# STM32F407.net
KiCad netlist of a schematic drawn in Altium Designer
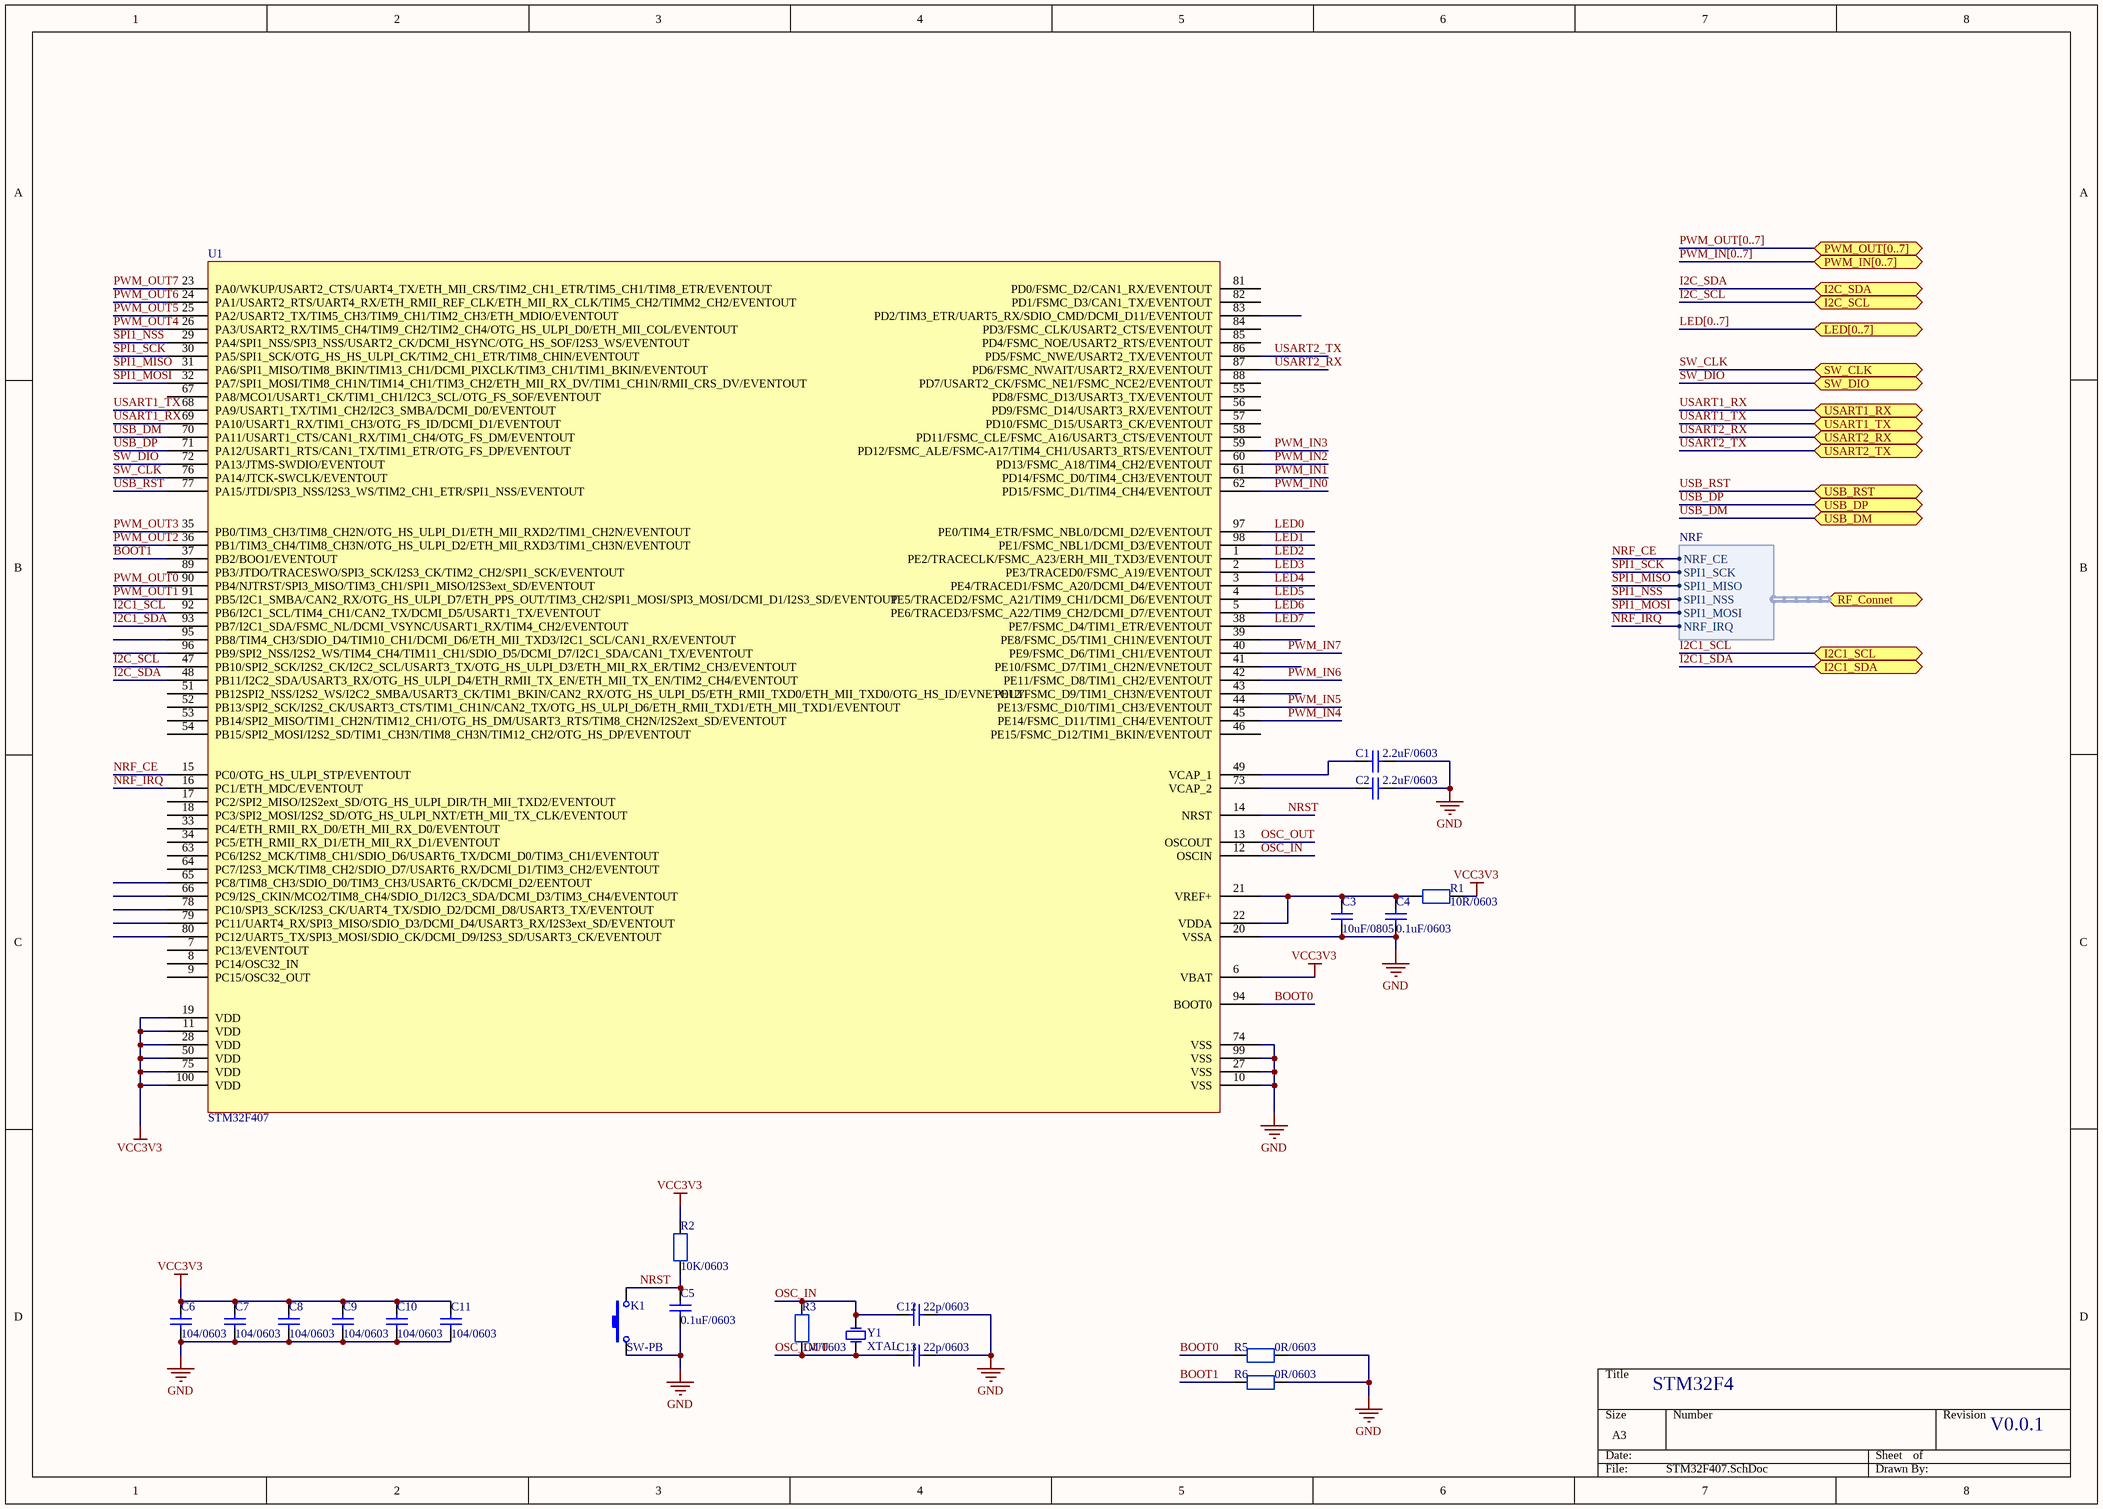
[diagram p0: STM32F407.SchDoc]

(export (version "E")
  (design (tool "Eeschema 10.0.6"))
  (components
    (comp (ref "C1")
      (value "2.2uF/0603")
      (footprint "C0603")
      (description "无极性贴片电容")
      (libsource (lib "常用原件") (part "CAP"))
    )
    (comp (ref "C2")
      (value "2.2uF/0603")
      (footprint "C0603")
      (description "无极性贴片电容")
      (libsource (lib "常用原件") (part "CAP"))
    )
    (comp (ref "C3")
      (value "10uF/0805")
      (footprint "C0805")
      (description "无极性贴片电容")
      (libsource (lib "常用原件") (part "CAP"))
    )
    (comp (ref "C4")
      (value "0.1uF/0603")
      (footprint "C0603")
      (description "无极性贴片电容")
      (libsource (lib "常用原件") (part "CAP"))
    )
    (comp (ref "C5")
      (value "0.1uF/0603")
      (footprint "C0603")
      (description "无极性贴片电容")
      (libsource (lib "常用原件") (part "CAP"))
    )
    (comp (ref "C6")
      (value "104/0603")
      (footprint "C0603")
      (description "无极性贴片电容")
      (libsource (lib "常用原件") (part "CAP"))
    )
    (comp (ref "C7")
      (value "104/0603")
      (footprint "C0603")
      (description "无极性贴片电容")
      (libsource (lib "常用原件") (part "CAP"))
    )
    (comp (ref "C8")
      (value "104/0603")
      (footprint "C0603")
      (description "无极性贴片电容")
      (libsource (lib "常用原件") (part "CAP"))
    )
    (comp (ref "C9")
      (value "104/0603")
      (footprint "C0603")
      (description "无极性贴片电容")
      (libsource (lib "常用原件") (part "CAP"))
    )
    (comp (ref "C10")
      (value "104/0603")
      (footprint "C0603")
      (description "无极性贴片电容")
      (libsource (lib "常用原件") (part "CAP"))
    )
    (comp (ref "C11")
      (value "104/0603")
      (footprint "C0603")
      (description "无极性贴片电容")
      (libsource (lib "常用原件") (part "CAP"))
    )
    (comp (ref "C12")
      (value "22p/0603")
      (footprint "C0603")
      (description "无极性贴片电容")
      (libsource (lib "常用原件") (part "CAP"))
    )
    (comp (ref "C13")
      (value "22p/0603")
      (footprint "C0603")
      (description "无极性贴片电容")
      (libsource (lib "常用原件") (part "CAP"))
    )
    (comp (ref "K1") (value "SW-PB") (footprint "SW-PB-A1") (libsource (lib "常用原件") (part "SW-PB")))
    (comp (ref "R1") (value "10R/0603") (footprint "R0603") (libsource (lib "常用原件") (part "RES")))
    (comp (ref "R2") (value "10K/0603") (footprint "R0603") (libsource (lib "常用原件") (part "RES")))
    (comp (ref "R3") (value "1M/0603") (footprint "R0603") (libsource (lib "常用原件") (part "RES")))
    (comp (ref "R5") (value "0R/0603") (footprint "R0603") (libsource (lib "常用原件") (part "RES")))
    (comp (ref "R6") (value "0R/0603") (footprint "R0402") (libsource (lib "常用原件") (part "RES")))
    (comp (ref "U1")
      (value "STM32F407")
      (footprint "LQFP100-N")
      (description "STM32F407VGT6")
      (libsource (lib "Schlib1") (part "STM32F4"))
    )
    (comp (ref "Y1") (value "XTAL") (footprint "XTAL-3225") (libsource (lib "库原理") (part "XTAL")))
  )
  (nets
    (net (code "2") (name "/BOOT0") (class "Default")
      (node (ref "R5") (pin "1") (pinfunction "1_1") (pintype "passive"))
      (node (ref "U1") (pin "94") (pinfunction "BOOT0_94") (pintype "passive"))
    )
    (net (code "3") (name "/BOOT1") (class "Default")
      (node (ref "R6") (pin "1") (pinfunction "1_1") (pintype "passive"))
      (node (ref "U1") (pin "37") (pinfunction "PB2/BOO1/EVENTOUT_37") (pintype "passive"))
    )
    (net (code "4") (name "/I2C1_SCL") (class "Default")
      (node (ref "U1") (pin "92") (pinfunction "PB6/I2C1_SCL/TIM4_CH1/CAN2_TX/DCMI_D5/USART1_TX/EVENTOUT_92") (pintype "passive"))
    )
    (net (code "5") (name "/I2C1_SDA") (class "Default")
      (node (ref "U1") (pin "93") (pinfunction "PB7/I2C1_SDA/FSMC_NL/DCMI_VSYNC/USART1_RX/TIM4_CH2/EVENTOUT_93") (pintype "passive"))
    )
    (net (code "6") (name "/I2C_SCL") (class "Default")
      (node (ref "U1") (pin "47") (pinfunction "PB10/SPI2_SCK/I2S2_CK/I2C2_SCL/USART3_TX/OTG_HS_ULPI_D3/ETH_MII_RX_ER/TIM2_CH3/EVENTOUT_47") (pintype "passive"))
    )
    (net (code "7") (name "/I2C_SDA") (class "Default")
      (node (ref "U1") (pin "48") (pinfunction "PB11/I2C2_SDA/USART3_RX/OTG_HS_ULPI_D4/ETH_RMII_TX_EN/ETH_MII_TX_EN/TIM2_CH4/EVENTOUT_48") (pintype "passive"))
    )
    (net (code "8") (name "/LED0") (class "Default")
      (node (ref "U1") (pin "97") (pinfunction "PE0/TIM4_ETR/FSMC_NBL0/DCMI_D2/EVENTOUT_97") (pintype "passive"))
    )
    (net (code "9") (name "/LED1") (class "Default")
      (node (ref "U1") (pin "98") (pinfunction "PE1/FSMC_NBL1/DCMI_D3/EVENTOUT_98") (pintype "passive"))
    )
    (net (code "10") (name "/LED2") (class "Default")
      (node (ref "U1") (pin "1") (pinfunction "PE2/TRACECLK/FSMC_A23/ERH_MII_TXD3/EVENTOUT_1") (pintype "passive"))
    )
    (net (code "11") (name "/LED3") (class "Default")
      (node (ref "U1") (pin "2") (pinfunction "PE3/TRACED0/FSMC_A19/EVENTOUT_2") (pintype "passive"))
    )
    (net (code "12") (name "/LED4") (class "Default")
      (node (ref "U1") (pin "3") (pinfunction "PE4/TRACED1/FSMC_A20/DCMI_D4/EVENTOUT_3") (pintype "passive"))
    )
    (net (code "13") (name "/LED5") (class "Default")
      (node (ref "U1") (pin "4") (pinfunction "PE5/TRACED2/FSMC_A21/TIM9_CH1/DCMI_D6/EVENTOUT_4") (pintype "passive"))
    )
    (net (code "14") (name "/LED6") (class "Default")
      (node (ref "U1") (pin "5") (pinfunction "PE6/TRACED3/FSMC_A22/TIM9_CH2/DCMI_D7/EVENTOUT_5") (pintype "passive"))
    )
    (net (code "15") (name "/LED7") (class "Default")
      (node (ref "U1") (pin "38") (pinfunction "PE7/FSMC_D4/TIM1_ETR/EVENTOUT_38") (pintype "passive"))
    )
    (net (code "17") (name "/NRF_CE") (class "Default")
      (node (ref "U1") (pin "15") (pinfunction "PC0/OTG_HS_ULPI_STP/EVENTOUT_15") (pintype "passive"))
    )
    (net (code "18") (name "/NRF_IRQ") (class "Default")
      (node (ref "U1") (pin "16") (pinfunction "PC1/ETH_MDC/EVENTOUT_16") (pintype "passive"))
    )
    (net (code "19") (name "/NRST") (class "Default")
      (node (ref "C5") (pin "2") (pinfunction "2_2") (pintype "passive"))
      (node (ref "K1") (pin "2") (pinfunction "2_2") (pintype "passive"))
      (node (ref "R2") (pin "1") (pinfunction "1_1") (pintype "passive"))
      (node (ref "U1") (pin "14") (pinfunction "NRST_14") (pintype "passive"))
    )
    (net (code "20") (name "/OSC_IN") (class "Default")
      (node (ref "C12") (pin "2") (pinfunction "2_2") (pintype "passive"))
      (node (ref "R3") (pin "2") (pinfunction "2_2") (pintype "passive"))
      (node (ref "U1") (pin "12") (pinfunction "OSCIN_12") (pintype "passive"))
      (node (ref "Y1") (pin "2") (pinfunction "OSC2_2") (pintype "passive"))
    )
    (net (code "21") (name "/OSC_OUT") (class "Default")
      (node (ref "C13") (pin "2") (pinfunction "2_2") (pintype "passive"))
      (node (ref "R3") (pin "1") (pinfunction "1_1") (pintype "passive"))
      (node (ref "U1") (pin "13") (pinfunction "OSCOUT_13") (pintype "passive"))
      (node (ref "Y1") (pin "1") (pinfunction "OSC1_1") (pintype "passive"))
    )
    (net (code "22") (name "/PWM_IN0") (class "Default")
      (node (ref "U1") (pin "62") (pinfunction "PD15/FSMC_D1/TIM4_CH4/EVENTOUT_62") (pintype "passive"))
    )
    (net (code "23") (name "/PWM_IN1") (class "Default")
      (node (ref "U1") (pin "61") (pinfunction "PD14/FSMC_D0/TIM4_CH3/EVENTOUT_61") (pintype "passive"))
    )
    (net (code "24") (name "/PWM_IN2") (class "Default")
      (node (ref "U1") (pin "60") (pinfunction "PD13/FSMC_A18/TIM4_CH2/EVENTOUT_60") (pintype "passive"))
    )
    (net (code "25") (name "/PWM_IN3") (class "Default")
      (node (ref "U1") (pin "59") (pinfunction "PD12/FSMC_ALE/FSMC-A17/TIM4_CH1/USART3_RTS/EVENTOUT_59") (pintype "passive"))
    )
    (net (code "26") (name "/PWM_IN4") (class "Default")
      (node (ref "U1") (pin "45") (pinfunction "PE14/FSMC_D11/TIM1_CH4/EVENTOUT_45") (pintype "passive"))
    )
    (net (code "27") (name "/PWM_IN5") (class "Default")
      (node (ref "U1") (pin "44") (pinfunction "PE13/FSMC_D10/TIM1_CH3/EVENTOUT_44") (pintype "passive"))
    )
    (net (code "28") (name "/PWM_IN6") (class "Default")
      (node (ref "U1") (pin "42") (pinfunction "PE11/FSMC_D8/TIM1_CH2/EVENTOUT_42") (pintype "passive"))
    )
    (net (code "29") (name "/PWM_IN7") (class "Default")
      (node (ref "U1") (pin "40") (pinfunction "PE9/FSMC_D6/TIM1_CH1/EVENTOUT_40") (pintype "passive"))
    )
    (net (code "31") (name "/PWM_OUT0") (class "Default")
      (node (ref "U1") (pin "90") (pinfunction "PB4/NJTRST/SPI3_MISO/TIM3_CH1/SPI1_MISO/I2S3ext_SD/EVENTOUT_90") (pintype "passive"))
    )
    (net (code "32") (name "/PWM_OUT1") (class "Default")
      (node (ref "U1") (pin "91") (pinfunction "PB5/I2C1_SMBA/CAN2_RX/OTG_HS_ULPI_D7/ETH_PPS_OUT/TIM3_CH2/SPI1_MOSI/SPI3_MOSI/DCMI_D1/I2S3_SD/EVENTOUT_91") (pintype "passive"))
    )
    (net (code "33") (name "/PWM_OUT2") (class "Default")
      (node (ref "U1") (pin "36") (pinfunction "PB1/TIM3_CH4/TIM8_CH3N/OTG_HS_ULPI_D2/ETH_MII_RXD3/TIM1_CH3N/EVENTOUT_36") (pintype "passive"))
    )
    (net (code "34") (name "/PWM_OUT3") (class "Default")
      (node (ref "U1") (pin "35") (pinfunction "PB0/TIM3_CH3/TIM8_CH2N/OTG_HS_ULPI_D1/ETH_MII_RXD2/TIM1_CH2N/EVENTOUT_35") (pintype "passive"))
    )
    (net (code "35") (name "/PWM_OUT4") (class "Default")
      (node (ref "U1") (pin "26") (pinfunction "PA3/USART2_RX/TIM5_CH4/TIM9_CH2/TIM2_CH4/OTG_HS_ULPI_D0/ETH_MII_COL/EVENTOUT_26") (pintype "passive"))
    )
    (net (code "36") (name "/PWM_OUT5") (class "Default")
      (node (ref "U1") (pin "25") (pinfunction "PA2/USART2_TX/TIM5_CH3/TIM9_CH1/TIM2_CH3/ETH_MDIO/EVENTOUT_25") (pintype "passive"))
    )
    (net (code "37") (name "/PWM_OUT6") (class "Default")
      (node (ref "U1") (pin "24") (pinfunction "PA1/USART2_RTS/UART4_RX/ETH_RMII_REF_CLK/ETH_MII_RX_CLK/TIM5_CH2/TIMM2_CH2/EVENTOUT_24") (pintype "passive"))
    )
    (net (code "38") (name "/PWM_OUT7") (class "Default")
      (node (ref "U1") (pin "23") (pinfunction "PA0/WKUP/USART2_CTS/UART4_TX/ETH_MII_CRS/TIM2_CH1_ETR/TIM5_CH1/TIM8_ETR/EVENTOUT_23") (pintype "passive"))
    )
    (net (code "40") (name "/SPI1_MISO") (class "Default")
      (node (ref "U1") (pin "31") (pinfunction "PA6/SPI1_MISO/TIM8_BKIN/TIM13_CH1/DCMI_PIXCLK/TIM3_CH1/TIM1_BKIN/EVENTOUT_31") (pintype "passive"))
    )
    (net (code "41") (name "/SPI1_MOSI") (class "Default")
      (node (ref "U1") (pin "32") (pinfunction "PA7/SPI1_MOSI/TIM8_CH1N/TIM14_CH1/TIM3_CH2/ETH_MII_RX_DV/TIM1_CH1N/RMII_CRS_DV/EVENTOUT_32") (pintype "passive"))
    )
    (net (code "42") (name "/SPI1_NSS") (class "Default")
      (node (ref "U1") (pin "29") (pinfunction "PA4/SPI1_NSS/SPI3_NSS/USART2_CK/DCMI_HSYNC/OTG_HS_SOF/I2S3_WS/EVENTOUT_29") (pintype "passive"))
    )
    (net (code "43") (name "/SPI1_SCK") (class "Default")
      (node (ref "U1") (pin "30") (pinfunction "PA5/SPI1_SCK/OTG_HS_HS_ULPI_CK/TIM2_CH1_ETR/TIM8_CHIN/EVENTOUT_30") (pintype "passive"))
    )
    (net (code "44") (name "/SW_CLK") (class "Default")
      (node (ref "U1") (pin "76") (pinfunction "PA14/JTCK-SWCLK/EVENTOUT_76") (pintype "passive"))
    )
    (net (code "45") (name "/SW_DIO") (class "Default")
      (node (ref "U1") (pin "72") (pinfunction "PA13/JTMS-SWDIO/EVENTOUT_72") (pintype "passive"))
    )
    (net (code "46") (name "/USART1_RX") (class "Default")
      (node (ref "U1") (pin "69") (pinfunction "PA10/USART1_RX/TIM1_CH3/OTG_FS_ID/DCMI_D1/EVENTOUT_69") (pintype "passive"))
    )
    (net (code "47") (name "/USART1_TX") (class "Default")
      (node (ref "U1") (pin "68") (pinfunction "PA9/USART1_TX/TIM1_CH2/I2C3_SMBA/DCMI_D0/EVENTOUT_68") (pintype "passive"))
    )
    (net (code "48") (name "/USART2_RX") (class "Default")
      (node (ref "U1") (pin "87") (pinfunction "PD6/FSMC_NWAIT/USART2_RX/EVENTOUT_87") (pintype "passive"))
    )
    (net (code "49") (name "/USART2_TX") (class "Default")
      (node (ref "U1") (pin "86") (pinfunction "PD5/FSMC_NWE/USART2_TX/EVENTOUT_86") (pintype "passive"))
    )
    (net (code "50") (name "/USB_DM") (class "Default")
      (node (ref "U1") (pin "70") (pinfunction "PA11/USART1_CTS/CAN1_RX/TIM1_CH4/OTG_FS_DM/EVENTOUT_70") (pintype "passive"))
    )
    (net (code "51") (name "/USB_DP") (class "Default")
      (node (ref "U1") (pin "71") (pinfunction "PA12/USART1_RTS/CAN1_TX/TIM1_ETR/OTG_FS_DP/EVENTOUT_71") (pintype "passive"))
    )
    (net (code "52") (name "/USB_RST") (class "Default")
      (node (ref "U1") (pin "77") (pinfunction "PA15/JTDI/SPI3_NSS/I2S3_WS/TIM2_CH1_ETR/SPI1_NSS/EVENTOUT_77") (pintype "passive"))
    )
    (net (code "54") (name "GND") (class "Default")
      (node (ref "C1") (pin "1") (pinfunction "1_1") (pintype "passive"))
      (node (ref "C10") (pin "1") (pinfunction "1_1") (pintype "passive"))
      (node (ref "C11") (pin "1") (pinfunction "1_1") (pintype "passive"))
      (node (ref "C12") (pin "1") (pinfunction "1_1") (pintype "passive"))
      (node (ref "C13") (pin "1") (pinfunction "1_1") (pintype "passive"))
      (node (ref "C2") (pin "1") (pinfunction "1_1") (pintype "passive"))
      (node (ref "C3") (pin "1") (pinfunction "1_1") (pintype "passive"))
      (node (ref "C4") (pin "1") (pinfunction "1_1") (pintype "passive"))
      (node (ref "C5") (pin "1") (pinfunction "1_1") (pintype "passive"))
      (node (ref "C6") (pin "1") (pinfunction "1_1") (pintype "passive"))
      (node (ref "C7") (pin "1") (pinfunction "1_1") (pintype "passive"))
      (node (ref "C8") (pin "1") (pinfunction "1_1") (pintype "passive"))
      (node (ref "C9") (pin "1") (pinfunction "1_1") (pintype "passive"))
      (node (ref "K1") (pin "1") (pinfunction "1_1") (pintype "passive"))
      (node (ref "R5") (pin "2") (pinfunction "2_2") (pintype "passive"))
      (node (ref "R6") (pin "2") (pinfunction "2_2") (pintype "passive"))
      (node (ref "U1") (pin "10") (pinfunction "VSS_10") (pintype "passive"))
      (node (ref "U1") (pin "20") (pinfunction "VSSA_20") (pintype "passive"))
      (node (ref "U1") (pin "27") (pinfunction "VSS_27") (pintype "passive"))
      (node (ref "U1") (pin "74") (pinfunction "VSS_74") (pintype "passive"))
      (node (ref "U1") (pin "99") (pinfunction "VSS_99") (pintype "passive"))
    )
    (net (code "55") (name "Net-(U1-VCAP_1)") (class "Default")
      (node (ref "C1") (pin "2") (pinfunction "2_2") (pintype "passive"))
      (node (ref "U1") (pin "49") (pinfunction "VCAP_1_49") (pintype "passive"))
    )
    (net (code "56") (name "Net-(U1-VCAP_2)") (class "Default")
      (node (ref "C2") (pin "2") (pinfunction "2_2") (pintype "passive"))
      (node (ref "U1") (pin "73") (pinfunction "VCAP_2_73") (pintype "passive"))
    )
    (net (code "57") (name "Net-(U1-VDDA)") (class "Default")
      (node (ref "C3") (pin "2") (pinfunction "2_2") (pintype "passive"))
      (node (ref "C4") (pin "2") (pinfunction "2_2") (pintype "passive"))
      (node (ref "R1") (pin "2") (pinfunction "2_2") (pintype "passive"))
      (node (ref "U1") (pin "21") (pinfunction "VREF+_21") (pintype "passive"))
      (node (ref "U1") (pin "22") (pinfunction "VDDA_22") (pintype "passive"))
    )
    (net (code "58") (name "VCC3V3") (class "Default")
      (node (ref "C10") (pin "2") (pinfunction "2_2") (pintype "passive"))
      (node (ref "C11") (pin "2") (pinfunction "2_2") (pintype "passive"))
      (node (ref "C6") (pin "2") (pinfunction "2_2") (pintype "passive"))
      (node (ref "C7") (pin "2") (pinfunction "2_2") (pintype "passive"))
      (node (ref "C8") (pin "2") (pinfunction "2_2") (pintype "passive"))
      (node (ref "C9") (pin "2") (pinfunction "2_2") (pintype "passive"))
      (node (ref "R1") (pin "1") (pinfunction "1_1") (pintype "passive"))
      (node (ref "R2") (pin "2") (pinfunction "2_2") (pintype "passive"))
      (node (ref "U1") (pin "100") (pinfunction "VDD_100") (pintype "passive"))
      (node (ref "U1") (pin "11") (pinfunction "VDD_11") (pintype "passive"))
      (node (ref "U1") (pin "19") (pinfunction "VDD_19") (pintype "passive"))
      (node (ref "U1") (pin "28") (pinfunction "VDD_28") (pintype "passive"))
      (node (ref "U1") (pin "50") (pinfunction "VDD_50") (pintype "passive"))
      (node (ref "U1") (pin "6") (pinfunction "VBAT_6") (pintype "passive"))
      (node (ref "U1") (pin "75") (pinfunction "VDD_75") (pintype "passive"))
    )
    (net (code "59") (name "unconnected-(U1-PA8{slash}MCO1{slash}USART1_CK{slash}TIM1_CH1{slash}I2C3_SCL{slash}OTG_FS_SOF{slash}EVENTOUT-Pad67)") (class "Default")
      (node (ref "U1") (pin "67") (pinfunction "PA8/MCO1/USART1_CK/TIM1_CH1/I2C3_SCL/OTG_FS_SOF/EVENTOUT_67") (pintype "passive"))
    )
    (net (code "60") (name "unconnected-(U1-PB3{slash}JTDO{slash}TRACESWO{slash}SPI3_SCK{slash}I2S3_CK{slash}TIM2_CH2{slash}SPI1_SCK{slash}EVENTOUT-Pad89)") (class "Default")
      (node (ref "U1") (pin "89") (pinfunction "PB3/JTDO/TRACESWO/SPI3_SCK/I2S3_CK/TIM2_CH2/SPI1_SCK/EVENTOUT_89") (pintype "passive"))
    )
    (net (code "61") (name "unconnected-(U1-PB8{slash}TIM4_CH3{slash}SDIO_D4{slash}TIM10_CH1{slash}DCMI_D6{slash}ETH_MII_TXD3{slash}I2C1_SCL{slash}CAN1_RX{slash}EVENTOUT-Pad95)") (class "Default")
      (node (ref "U1") (pin "95") (pinfunction "PB8/TIM4_CH3/SDIO_D4/TIM10_CH1/DCMI_D6/ETH_MII_TXD3/I2C1_SCL/CAN1_RX/EVENTOUT_95") (pintype "passive"))
    )
    (net (code "62") (name "unconnected-(U1-PB9{slash}SPI2_NSS{slash}I2S2_WS{slash}TIM4_CH4{slash}TIM11_CH1{slash}SDIO_D5{slash}DCMI_D7{slash}I2C1_SDA{slash}CAN1_TX{slash}EVENTOUT-Pad96)") (class "Default")
      (node (ref "U1") (pin "96") (pinfunction "PB9/SPI2_NSS/I2S2_WS/TIM4_CH4/TIM11_CH1/SDIO_D5/DCMI_D7/I2C1_SDA/CAN1_TX/EVENTOUT_96") (pintype "passive"))
    )
    (net (code "63") (name "unconnected-(U1-PB12SPI2_NSS{slash}I2S2_WS{slash}I2C2_SMBA{slash}USART3_CK{slash}TIM1_BKIN{slash}CAN2_RX{slash}OTG_HS_ULPI_D5{slash}ETH_RMII_TXD0{slash}ETH_MII_TXD0{slash}OTG_HS_ID{slash}EVNETOUT-Pad51)") (class "Default")
      (node (ref "U1") (pin "51") (pinfunction "PB12SPI2_NSS/I2S2_WS/I2C2_SMBA/USART3_CK/TIM1_BKIN/CAN2_RX/OTG_HS_ULPI_D5/ETH_RMII_TXD0/ETH_MII_TXD0/OTG_HS_ID/EVNETOUT_51") (pintype "passive"))
    )
    (net (code "64") (name "unconnected-(U1-PB13{slash}SPI2_SCK{slash}I2S2_CK{slash}USART3_CTS{slash}TIM1_CH1N{slash}CAN2_TX{slash}OTG_HS_ULPI_D6{slash}ETH_RMII_TXD1{slash}ETH_MII_TXD1{slash}EVENTOUT-Pad52)") (class "Default")
      (node (ref "U1") (pin "52") (pinfunction "PB13/SPI2_SCK/I2S2_CK/USART3_CTS/TIM1_CH1N/CAN2_TX/OTG_HS_ULPI_D6/ETH_RMII_TXD1/ETH_MII_TXD1/EVENTOUT_52") (pintype "passive"))
    )
    (net (code "65") (name "unconnected-(U1-PB14{slash}SPI2_MISO{slash}TIM1_CH2N{slash}TIM12_CH1{slash}OTG_HS_DM{slash}USART3_RTS{slash}TIM8_CH2N{slash}I2S2ext_SD{slash}EVENTOUT-Pad53)") (class "Default")
      (node (ref "U1") (pin "53") (pinfunction "PB14/SPI2_MISO/TIM1_CH2N/TIM12_CH1/OTG_HS_DM/USART3_RTS/TIM8_CH2N/I2S2ext_SD/EVENTOUT_53") (pintype "passive"))
    )
    (net (code "66") (name "unconnected-(U1-PB15{slash}SPI2_MOSI{slash}I2S2_SD{slash}TIM1_CH3N{slash}TIM8_CH3N{slash}TIM12_CH2{slash}OTG_HS_DP{slash}EVENTOUT-Pad54)") (class "Default")
      (node (ref "U1") (pin "54") (pinfunction "PB15/SPI2_MOSI/I2S2_SD/TIM1_CH3N/TIM8_CH3N/TIM12_CH2/OTG_HS_DP/EVENTOUT_54") (pintype "passive"))
    )
    (net (code "67") (name "unconnected-(U1-PC2{slash}SPI2_MISO{slash}I2S2ext_SD{slash}OTG_HS_ULPI_DIR{slash}TH_MII_TXD2{slash}EVENTOUT-Pad17)") (class "Default")
      (node (ref "U1") (pin "17") (pinfunction "PC2/SPI2_MISO/I2S2ext_SD/OTG_HS_ULPI_DIR/TH_MII_TXD2/EVENTOUT_17") (pintype "passive"))
    )
    (net (code "68") (name "unconnected-(U1-PC3{slash}SPI2_MOSI{slash}I2S2_SD{slash}OTG_HS_ULPI_NXT{slash}ETH_MII_TX_CLK{slash}EVENTOUT-Pad18)") (class "Default")
      (node (ref "U1") (pin "18") (pinfunction "PC3/SPI2_MOSI/I2S2_SD/OTG_HS_ULPI_NXT/ETH_MII_TX_CLK/EVENTOUT_18") (pintype "passive"))
    )
    (net (code "69") (name "unconnected-(U1-PC4{slash}ETH_RMII_RX_D0{slash}ETH_MII_RX_D0{slash}EVENTOUT-Pad33)") (class "Default")
      (node (ref "U1") (pin "33") (pinfunction "PC4/ETH_RMII_RX_D0/ETH_MII_RX_D0/EVENTOUT_33") (pintype "passive"))
    )
    (net (code "70") (name "unconnected-(U1-PC5{slash}ETH_RMII_RX_D1{slash}ETH_MII_RX_D1{slash}EVENTOUT-Pad34)") (class "Default")
      (node (ref "U1") (pin "34") (pinfunction "PC5/ETH_RMII_RX_D1/ETH_MII_RX_D1/EVENTOUT_34") (pintype "passive"))
    )
    (net (code "71") (name "unconnected-(U1-PC6{slash}I2S2_MCK{slash}TIM8_CH1{slash}SDIO_D6{slash}USART6_TX{slash}DCMI_D0{slash}TIM3_CH1{slash}EVENTOUT-Pad63)") (class "Default")
      (node (ref "U1") (pin "63") (pinfunction "PC6/I2S2_MCK/TIM8_CH1/SDIO_D6/USART6_TX/DCMI_D0/TIM3_CH1/EVENTOUT_63") (pintype "passive"))
    )
    (net (code "72") (name "unconnected-(U1-PC7{slash}I2S3_MCK{slash}TIM8_CH2{slash}SDIO_D7{slash}USART6_RX{slash}DCMI_D1{slash}TIM3_CH2{slash}EVENTOUT-Pad64)") (class "Default")
      (node (ref "U1") (pin "64") (pinfunction "PC7/I2S3_MCK/TIM8_CH2/SDIO_D7/USART6_RX/DCMI_D1/TIM3_CH2/EVENTOUT_64") (pintype "passive"))
    )
    (net (code "73") (name "unconnected-(U1-PC8{slash}TIM8_CH3{slash}SDIO_D0{slash}TIM3_CH3{slash}USART6_CK{slash}DCMI_D2{slash}EENTOUT-Pad65)") (class "Default")
      (node (ref "U1") (pin "65") (pinfunction "PC8/TIM8_CH3/SDIO_D0/TIM3_CH3/USART6_CK/DCMI_D2/EENTOUT_65") (pintype "passive"))
    )
    (net (code "74") (name "unconnected-(U1-PC9{slash}I2S_CKIN{slash}MCO2{slash}TIM8_CH4{slash}SDIO_D1{slash}I2C3_SDA{slash}DCMI_D3{slash}TIM3_CH4{slash}EVENTOUT-Pad66)") (class "Default")
      (node (ref "U1") (pin "66") (pinfunction "PC9/I2S_CKIN/MCO2/TIM8_CH4/SDIO_D1/I2C3_SDA/DCMI_D3/TIM3_CH4/EVENTOUT_66") (pintype "passive"))
    )
    (net (code "75") (name "unconnected-(U1-PC10{slash}SPI3_SCK{slash}I2S3_CK{slash}UART4_TX{slash}SDIO_D2{slash}DCMI_D8{slash}USART3_TX{slash}EVENTOUT-Pad78)") (class "Default")
      (node (ref "U1") (pin "78") (pinfunction "PC10/SPI3_SCK/I2S3_CK/UART4_TX/SDIO_D2/DCMI_D8/USART3_TX/EVENTOUT_78") (pintype "passive"))
    )
    (net (code "76") (name "unconnected-(U1-PC11{slash}UART4_RX{slash}SPI3_MISO{slash}SDIO_D3{slash}DCMI_D4{slash}USART3_RX{slash}I2S3ext_SD{slash}EVENTOUT-Pad79)") (class "Default")
      (node (ref "U1") (pin "79") (pinfunction "PC11/UART4_RX/SPI3_MISO/SDIO_D3/DCMI_D4/USART3_RX/I2S3ext_SD/EVENTOUT_79") (pintype "passive"))
    )
    (net (code "77") (name "unconnected-(U1-PC12{slash}UART5_TX{slash}SPI3_MOSI{slash}SDIO_CK{slash}DCMI_D9{slash}I2S3_SD{slash}USART3_CK{slash}EVENTOUT-Pad80)") (class "Default")
      (node (ref "U1") (pin "80") (pinfunction "PC12/UART5_TX/SPI3_MOSI/SDIO_CK/DCMI_D9/I2S3_SD/USART3_CK/EVENTOUT_80") (pintype "passive"))
    )
    (net (code "78") (name "unconnected-(U1-PC13{slash}EVENTOUT-Pad7)") (class "Default")
      (node (ref "U1") (pin "7") (pinfunction "PC13/EVENTOUT_7") (pintype "passive"))
    )
    (net (code "79") (name "unconnected-(U1-PC14{slash}OSC32_IN-Pad8)") (class "Default")
      (node (ref "U1") (pin "8") (pinfunction "PC14/OSC32_IN_8") (pintype "passive"))
    )
    (net (code "80") (name "unconnected-(U1-PC15{slash}OSC32_OUT-Pad9)") (class "Default")
      (node (ref "U1") (pin "9") (pinfunction "PC15/OSC32_OUT_9") (pintype "passive"))
    )
    (net (code "81") (name "unconnected-(U1-PD0{slash}FSMC_D2{slash}CAN1_RX{slash}EVENTOUT-Pad81)") (class "Default")
      (node (ref "U1") (pin "81") (pinfunction "PD0/FSMC_D2/CAN1_RX/EVENTOUT_81") (pintype "passive"))
    )
    (net (code "82") (name "unconnected-(U1-PD1{slash}FSMC_D3{slash}CAN1_TX{slash}EVENTOUT-Pad82)") (class "Default")
      (node (ref "U1") (pin "82") (pinfunction "PD1/FSMC_D3/CAN1_TX/EVENTOUT_82") (pintype "passive"))
    )
    (net (code "83") (name "unconnected-(U1-PD2{slash}TIM3_ETR{slash}UART5_RX{slash}SDIO_CMD{slash}DCMI_D11{slash}EVENTOUT-Pad83)") (class "Default")
      (node (ref "U1") (pin "83") (pinfunction "PD2/TIM3_ETR/UART5_RX/SDIO_CMD/DCMI_D11/EVENTOUT_83") (pintype "passive"))
    )
    (net (code "84") (name "unconnected-(U1-PD3{slash}FSMC_CLK{slash}USART2_CTS{slash}EVENTOUT-Pad84)") (class "Default")
      (node (ref "U1") (pin "84") (pinfunction "PD3/FSMC_CLK/USART2_CTS/EVENTOUT_84") (pintype "passive"))
    )
    (net (code "85") (name "unconnected-(U1-PD4{slash}FSMC_NOE{slash}USART2_RTS{slash}EVENTOUT-Pad85)") (class "Default")
      (node (ref "U1") (pin "85") (pinfunction "PD4/FSMC_NOE/USART2_RTS/EVENTOUT_85") (pintype "passive"))
    )
    (net (code "86") (name "unconnected-(U1-PD7{slash}USART2_CK{slash}FSMC_NE1{slash}FSMC_NCE2{slash}EVENTOUT-Pad88)") (class "Default")
      (node (ref "U1") (pin "88") (pinfunction "PD7/USART2_CK/FSMC_NE1/FSMC_NCE2/EVENTOUT_88") (pintype "passive"))
    )
    (net (code "87") (name "unconnected-(U1-PD8{slash}FSMC_D13{slash}USART3_TX{slash}EVENTOUT-Pad55)") (class "Default")
      (node (ref "U1") (pin "55") (pinfunction "PD8/FSMC_D13/USART3_TX/EVENTOUT_55") (pintype "passive"))
    )
    (net (code "88") (name "unconnected-(U1-PD9{slash}FSMC_D14{slash}USART3_RX{slash}EVENTOUT-Pad56)") (class "Default")
      (node (ref "U1") (pin "56") (pinfunction "PD9/FSMC_D14/USART3_RX/EVENTOUT_56") (pintype "passive"))
    )
    (net (code "89") (name "unconnected-(U1-PD10{slash}FSMC_D15{slash}USART3_CK{slash}EVENTOUT-Pad57)") (class "Default")
      (node (ref "U1") (pin "57") (pinfunction "PD10/FSMC_D15/USART3_CK/EVENTOUT_57") (pintype "passive"))
    )
    (net (code "90") (name "unconnected-(U1-PD11{slash}FSMC_CLE{slash}FSMC_A16{slash}USART3_CTS{slash}EVENTOUT-Pad58)") (class "Default")
      (node (ref "U1") (pin "58") (pinfunction "PD11/FSMC_CLE/FSMC_A16/USART3_CTS/EVENTOUT_58") (pintype "passive"))
    )
    (net (code "91") (name "unconnected-(U1-PE8{slash}FSMC_D5{slash}TIM1_CH1N{slash}EVENTOUT-Pad39)") (class "Default")
      (node (ref "U1") (pin "39") (pinfunction "PE8/FSMC_D5/TIM1_CH1N/EVENTOUT_39") (pintype "passive"))
    )
    (net (code "92") (name "unconnected-(U1-PE10{slash}FSMC_D7{slash}TIM1_CH2N{slash}EVNETOUT-Pad41)") (class "Default")
      (node (ref "U1") (pin "41") (pinfunction "PE10/FSMC_D7/TIM1_CH2N/EVNETOUT_41") (pintype "passive"))
    )
    (net (code "93") (name "unconnected-(U1-PE12{slash}FSMC_D9{slash}TIM1_CH3N{slash}EVENTOUT-Pad43)") (class "Default")
      (node (ref "U1") (pin "43") (pinfunction "PE12/FSMC_D9/TIM1_CH3N/EVENTOUT_43") (pintype "passive"))
    )
    (net (code "94") (name "unconnected-(U1-PE15{slash}FSMC_D12{slash}TIM1_BKIN{slash}EVENTOUT-Pad46)") (class "Default")
      (node (ref "U1") (pin "46") (pinfunction "PE15/FSMC_D12/TIM1_BKIN/EVENTOUT_46") (pintype "passive"))
    )
  )
)
